# MEDICION_CORRIENTE.net
KiCad netlist of a schematic drawn in Altium Designer
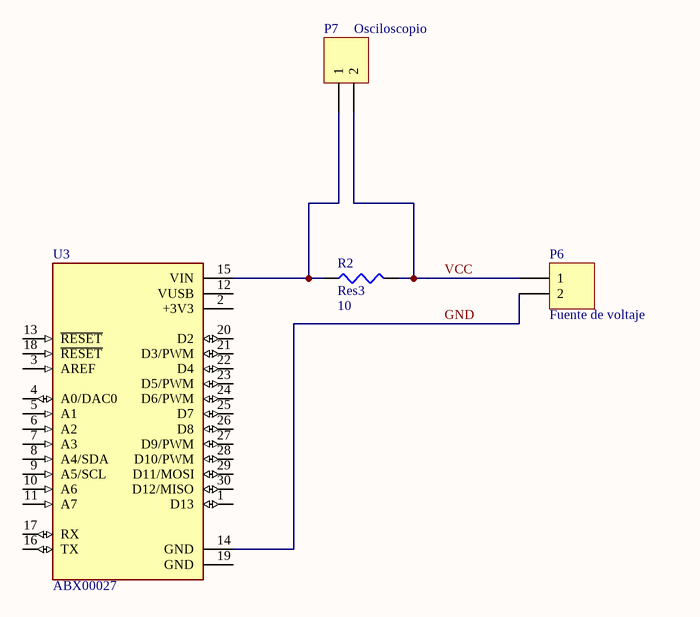
[diagram p0: MEDICION_CORRIENTE.SchDoc]

(export (version "E")
  (design (tool "Eeschema 10.0.6"))
  (components
    (comp (ref "P6")
      (value "Fuente de voltaje")
      (footprint "HDR1X2")
      (description "Header, 2-Pin")
      (fields (field (name "PUBLISHER") "Altium Limited"))
      (libsource (lib "") (part "Header 2_1"))
    )
    (comp (ref "P7")
      (value "Osciloscopio")
      (footprint "HDR1X2")
      (description "Header, 2-Pin")
      (fields (field (name "PUBLISHER") "Altium Limited"))
      (libsource (lib "Miscellaneous Connectors") (part "Header 2"))
    )
    (comp (ref "R2")
      (value "Res3")
      (footprint "J1-0603")
      (description "Resistor")
      (fields (field (name "ALTIUM_VALUE") "10") (field (name "PUBLISHER") "Altium Limited"))
      (libsource (lib "Miscellaneous Devices") (part "Res3"))
    )
    (comp (ref "U3")
      (value "ABX00027")
      (footprint "MODULE_ABX00027")
      (description "ATSAMD21G18A Arduino Nano 33 IoT SAM D ARMÂ® CortexÂ®-M0+ MCU 32-Bit Embedded Evaluation Board")
      (fields (field (name "MF") "{'manufacturer': u'Arduino'}"))
      (libsource (lib "SnapEDA_Library") (part "ABX00027"))
    )
  )
  (nets
    (net (code "1") (name "/GND") (class "Default")
      (node (ref "P6") (pin "2") (pinfunction "2_2") (pintype "passive"))
      (node (ref "U3") (pin "14") (pinfunction "GND_14") (pintype "power_in"))
    )
    (net (code "2") (name "/VCC") (class "Default")
      (node (ref "P6") (pin "1") (pinfunction "1_1") (pintype "passive"))
      (node (ref "P7") (pin "2") (pinfunction "2_2") (pintype "passive"))
      (node (ref "R2") (pin "2") (pinfunction "2_2") (pintype "passive"))
    )
    (net (code "3") (name "Net-(U3-VIN)") (class "Default")
      (node (ref "P7") (pin "1") (pinfunction "1_1") (pintype "passive"))
      (node (ref "R2") (pin "1") (pinfunction "1_1") (pintype "passive"))
      (node (ref "U3") (pin "15") (pinfunction "VIN_15") (pintype "power_in"))
    )
    (net (code "4") (name "unconnected-(U3-+3V3-Pad2)") (class "Default")
      (node (ref "U3") (pin "2") (pinfunction "+3V3_2") (pintype "power_in"))
    )
    (net (code "5") (name "unconnected-(U3-A0{slash}DAC0-Pad4)") (class "Default")
      (node (ref "U3") (pin "4") (pinfunction "A0/DAC0_4") (pintype "bidirectional"))
    )
    (net (code "6") (name "unconnected-(U3-A1-Pad5)") (class "Default")
      (node (ref "U3") (pin "5") (pinfunction "A1_5") (pintype "input"))
    )
    (net (code "7") (name "unconnected-(U3-A2-Pad6)") (class "Default")
      (node (ref "U3") (pin "6") (pinfunction "A2_6") (pintype "input"))
    )
    (net (code "8") (name "unconnected-(U3-A3-Pad7)") (class "Default")
      (node (ref "U3") (pin "7") (pinfunction "A3_7") (pintype "input"))
    )
    (net (code "9") (name "unconnected-(U3-A4{slash}SDA-Pad8)") (class "Default")
      (node (ref "U3") (pin "8") (pinfunction "A4/SDA_8") (pintype "input"))
    )
    (net (code "10") (name "unconnected-(U3-A5{slash}SCL-Pad9)") (class "Default")
      (node (ref "U3") (pin "9") (pinfunction "A5/SCL_9") (pintype "input"))
    )
    (net (code "11") (name "unconnected-(U3-A6-Pad10)") (class "Default")
      (node (ref "U3") (pin "10") (pinfunction "A6_10") (pintype "input"))
    )
    (net (code "12") (name "unconnected-(U3-A7-Pad11)") (class "Default")
      (node (ref "U3") (pin "11") (pinfunction "A7_11") (pintype "input"))
    )
    (net (code "13") (name "unconnected-(U3-AREF-Pad3)") (class "Default")
      (node (ref "U3") (pin "3") (pinfunction "AREF_3") (pintype "input"))
    )
    (net (code "14") (name "unconnected-(U3-D2-Pad20)") (class "Default")
      (node (ref "U3") (pin "20") (pinfunction "D2_20") (pintype "bidirectional"))
    )
    (net (code "15") (name "unconnected-(U3-D3{slash}PWM-Pad21)") (class "Default")
      (node (ref "U3") (pin "21") (pinfunction "D3/PWM_21") (pintype "bidirectional"))
    )
    (net (code "16") (name "unconnected-(U3-D4-Pad22)") (class "Default")
      (node (ref "U3") (pin "22") (pinfunction "D4_22") (pintype "bidirectional"))
    )
    (net (code "17") (name "unconnected-(U3-D5{slash}PWM-Pad23)") (class "Default")
      (node (ref "U3") (pin "23") (pinfunction "D5/PWM_23") (pintype "bidirectional"))
    )
    (net (code "18") (name "unconnected-(U3-D6{slash}PWM-Pad24)") (class "Default")
      (node (ref "U3") (pin "24") (pinfunction "D6/PWM_24") (pintype "bidirectional"))
    )
    (net (code "19") (name "unconnected-(U3-D7-Pad25)") (class "Default")
      (node (ref "U3") (pin "25") (pinfunction "D7_25") (pintype "bidirectional"))
    )
    (net (code "20") (name "unconnected-(U3-D8-Pad26)") (class "Default")
      (node (ref "U3") (pin "26") (pinfunction "D8_26") (pintype "bidirectional"))
    )
    (net (code "21") (name "unconnected-(U3-D9{slash}PWM-Pad27)") (class "Default")
      (node (ref "U3") (pin "27") (pinfunction "D9/PWM_27") (pintype "bidirectional"))
    )
    (net (code "22") (name "unconnected-(U3-D10{slash}PWM-Pad28)") (class "Default")
      (node (ref "U3") (pin "28") (pinfunction "D10/PWM_28") (pintype "bidirectional"))
    )
    (net (code "23") (name "unconnected-(U3-D11{slash}MOSI-Pad29)") (class "Default")
      (node (ref "U3") (pin "29") (pinfunction "D11/MOSI_29") (pintype "bidirectional"))
    )
    (net (code "24") (name "unconnected-(U3-D12{slash}MISO-Pad30)") (class "Default")
      (node (ref "U3") (pin "30") (pinfunction "D12/MISO_30") (pintype "bidirectional"))
    )
    (net (code "25") (name "unconnected-(U3-D13-Pad1)") (class "Default")
      (node (ref "U3") (pin "1") (pinfunction "D13_1") (pintype "bidirectional"))
    )
    (net (code "26") (name "unconnected-(U3-GND-Pad19)") (class "Default")
      (node (ref "U3") (pin "19") (pinfunction "GND_19") (pintype "power_in"))
    )
    (net (code "27") (name "unconnected-(U3-RX-Pad17)") (class "Default")
      (node (ref "U3") (pin "17") (pinfunction "RX_17") (pintype "bidirectional"))
    )
    (net (code "28") (name "unconnected-(U3-TX-Pad16)") (class "Default")
      (node (ref "U3") (pin "16") (pinfunction "TX_16") (pintype "bidirectional"))
    )
    (net (code "29") (name "unconnected-(U3-VUSB-Pad12)") (class "Default")
      (node (ref "U3") (pin "12") (pinfunction "VUSB_12") (pintype "power_in"))
    )
    (net (code "30") (name "unconnected-(U3-~{RESET}-Pad13)") (class "Default")
      (node (ref "U3") (pin "13") (pinfunction "~{RESET}_13") (pintype "input"))
    )
    (net (code "31") (name "unconnected-(U3-~{RESET}-Pad18)") (class "Default")
      (node (ref "U3") (pin "18") (pinfunction "~{RESET}_18") (pintype "input"))
    )
  )
)
